# LM2576_Buck_Converter.net
KiCad netlist of a schematic drawn in Altium Designer
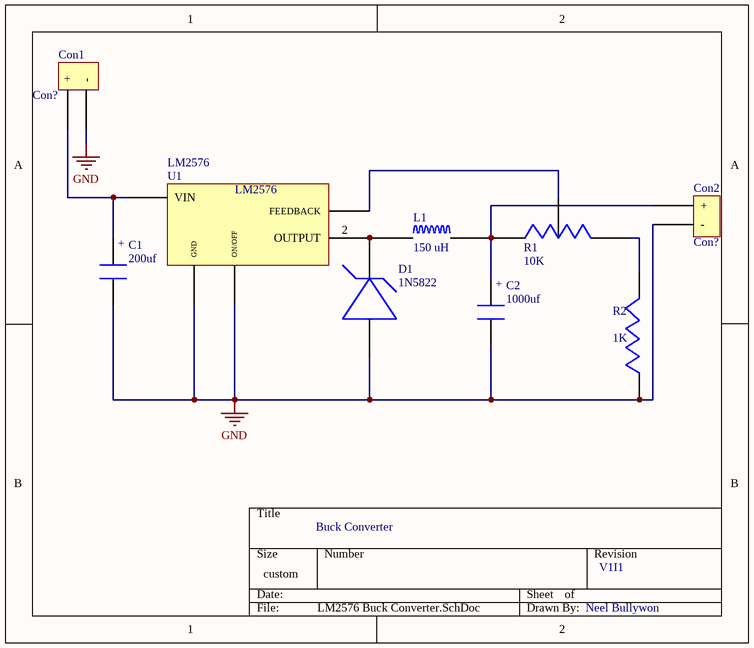
[diagram p0: LM2576 Buck Converter.SchDoc]

(export (version "E")
  (design (tool "Eeschema 10.0.6"))
  (components
    (comp (ref "C1")
      (value "200uf")
      (footprint "220uF Capacitor")
      (libsource (lib "Schlib1") (part "Electrolytic Capacitor"))
    )
    (comp (ref "C2")
      (value "1000uf")
      (footprint "1000Uf Cap")
      (libsource (lib "Schlib1") (part "Electrolytic Capacitor"))
    )
    (comp (ref "Con1") (value "Con?") (footprint "2pin") (libsource (lib "") (part "2PinConnector_1")))
    (comp (ref "Con2") (value "Con?") (footprint "2pin") (libsource (lib "Schlib1") (part "2PinConnector")))
    (comp (ref "D1") (value "1N5822") (footprint "1n5822") (libsource (lib "Schlib1") (part "1N5822")))
    (comp (ref "L1")
      (value "150 uH")
      (footprint "150uH Inductor")
      (libsource (lib "Schlib1") (part "150UH L"))
    )
    (comp (ref "R1")
      (value "10K")
      (footprint "10K Pot")
      (libsource (lib "Schlib1") (part "Variable Resistor"))
    )
    (comp (ref "R2") (value "1K") (footprint "1K 1206 Res") (libsource (lib "Schlib1") (part "Resistor")))
    (comp (ref "U1") (value "LM2576") (footprint "LM2576-TO63-5") (libsource (lib "Schlib1") (part "LM2576")))
  )
  (nets
    (net (code "1") (name "GND") (class "Default")
      (node (ref "C1") (pin "2") (pinfunction "2_2") (pintype "passive"))
      (node (ref "C2") (pin "2") (pinfunction "2_2") (pintype "passive"))
      (node (ref "Con1") (pin "2") (pinfunction "-_2") (pintype "passive"))
      (node (ref "Con2") (pin "2") (pinfunction "-_2") (pintype "passive"))
      (node (ref "D1") (pin "2") (pinfunction "2_2") (pintype "passive"))
      (node (ref "R2") (pin "1") (pinfunction "1_1") (pintype "passive"))
      (node (ref "U1") (pin "3") (pinfunction "GND_3") (pintype "passive"))
      (node (ref "U1") (pin "5") (pinfunction "ON/OFF_5") (pintype "passive"))
    )
    (net (code "2") (name "Net-(Con1-+)") (class "Default")
      (node (ref "C1") (pin "1") (pinfunction "1_1") (pintype "passive"))
      (node (ref "Con1") (pin "1") (pinfunction "+_1") (pintype "passive"))
      (node (ref "U1") (pin "1") (pinfunction "VIN_1") (pintype "passive"))
    )
    (net (code "3") (name "Net-(Con2-+)") (class "Default")
      (node (ref "C2") (pin "1") (pinfunction "1_1") (pintype "passive"))
      (node (ref "Con2") (pin "1") (pinfunction "+_1") (pintype "passive"))
      (node (ref "L1") (pin "2") (pinfunction "2_2") (pintype "passive"))
    )
    (net (code "4") (name "Net-(R1-Pad3)") (class "Default")
      (node (ref "R1") (pin "3") (pinfunction "3_3") (pintype "passive"))
      (node (ref "R2") (pin "2") (pinfunction "2_2") (pintype "passive"))
    )
    (net (code "5") (name "Net-(U1-FEEDBACK)") (class "Default")
      (node (ref "R1") (pin "2") (pinfunction "2_2") (pintype "passive"))
      (node (ref "U1") (pin "4") (pinfunction "FEEDBACK_4") (pintype "passive"))
    )
    (net (code "6") (name "Net-(U1-OUTPUT)") (class "Default")
      (node (ref "D1") (pin "1") (pinfunction "1_1") (pintype "passive"))
      (node (ref "L1") (pin "1") (pinfunction "1_1") (pintype "passive"))
      (node (ref "U1") (pin "2") (pinfunction "OUTPUT_2") (pintype "passive"))
    )
    (net (code "7") (name "unconnected-(R1-Pad1)") (class "Default")
      (node (ref "R1") (pin "1") (pinfunction "1_1") (pintype "passive"))
    )
  )
)
